# untitled.net
KiCad netlist of a schematic drawn in EAGLE
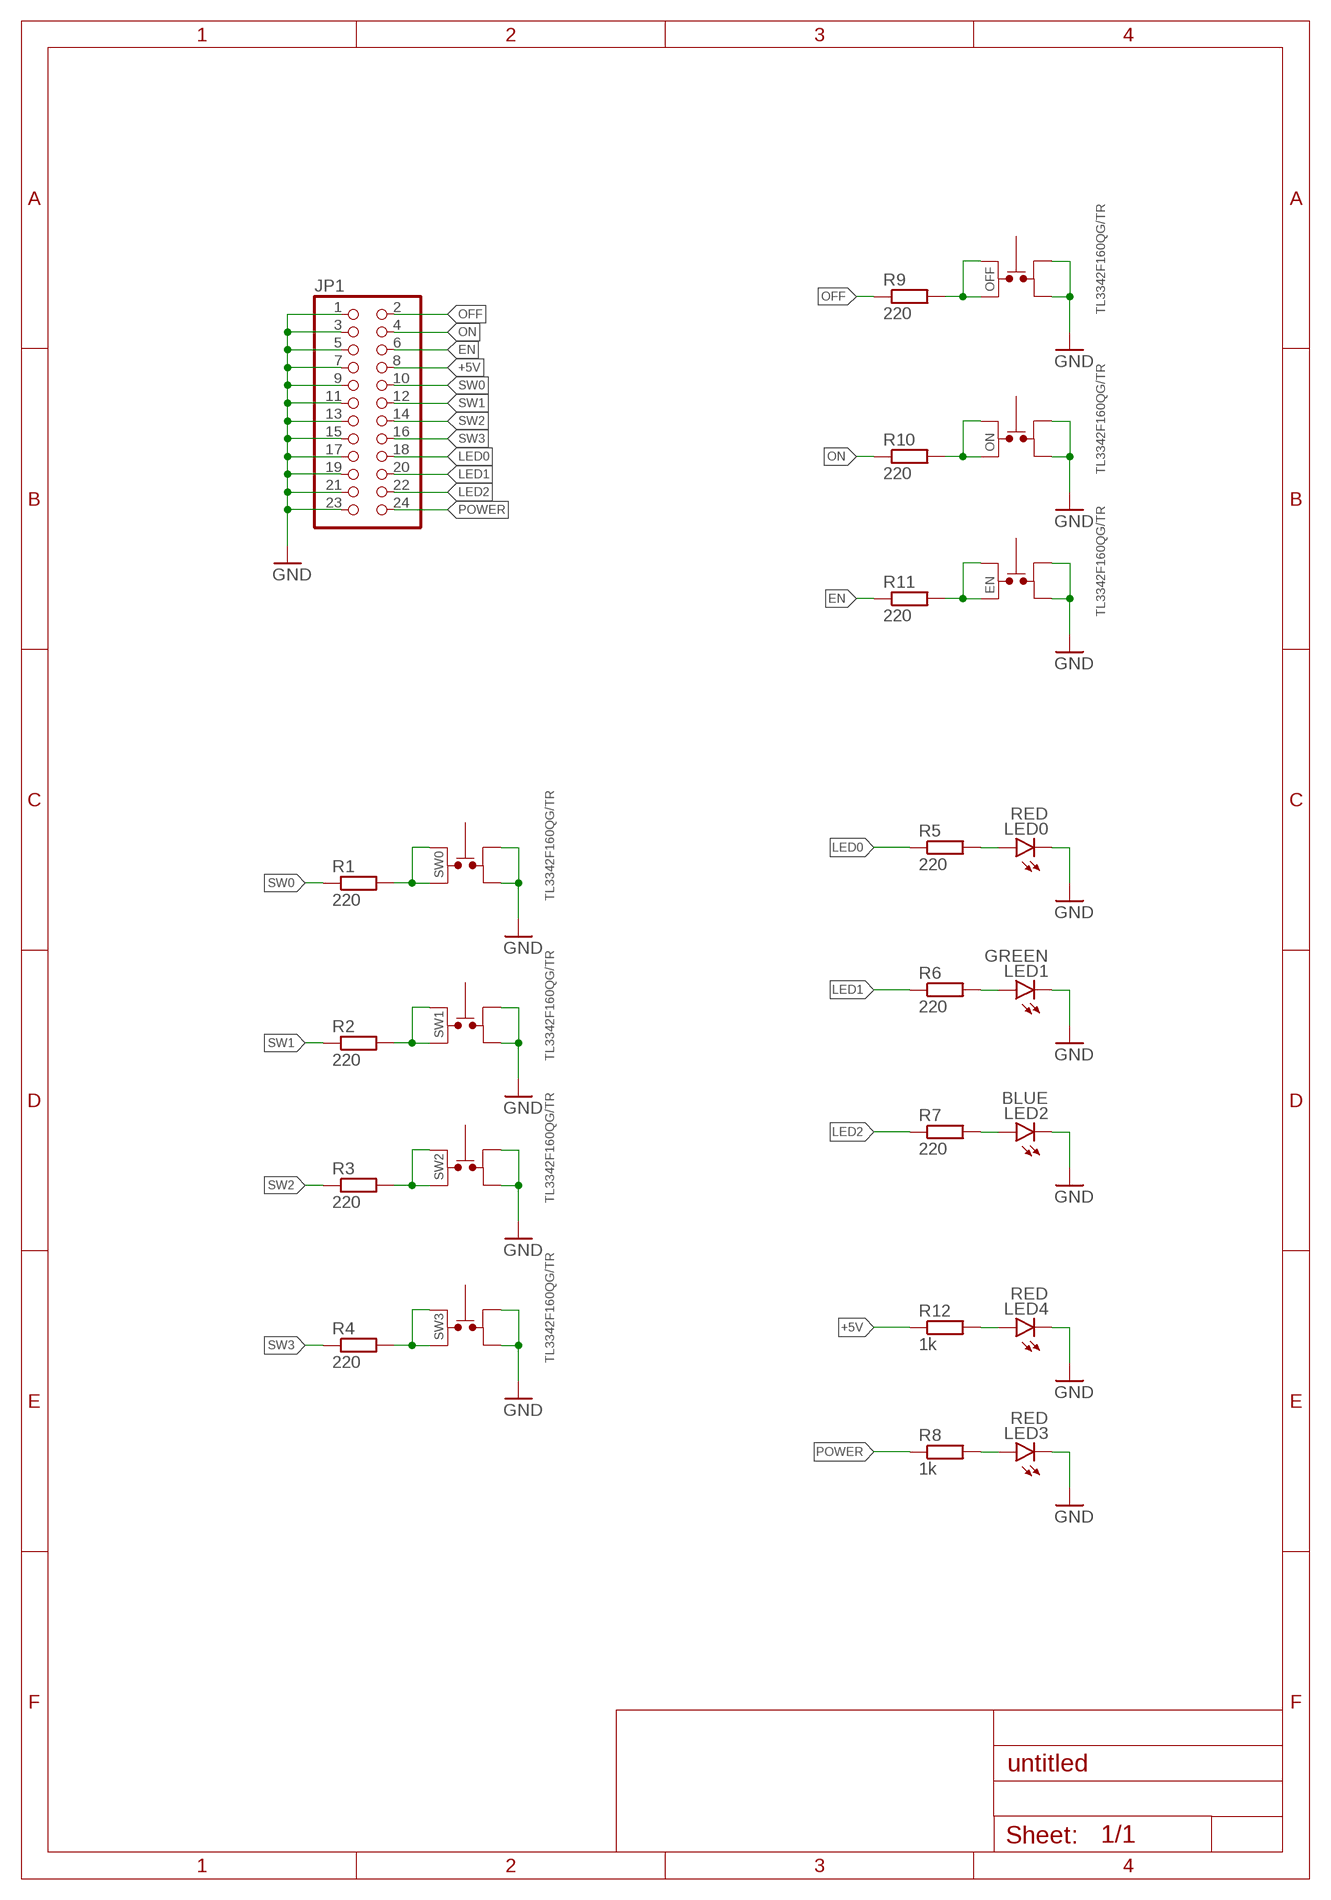
[diagram p0: schematic, sheet 1]

(export (version "E")
  (design (tool "Eeschema 10.0.6"))
  (components
    (comp (ref "EN")
      (value "TL3342F160QG/TR")
      (footprint "eagle-import:TL3342F160QG_TR")
      (fields
        (field (name "DIGI_KEY_PART_NUMBER") "EG2531CT-ND")
        (field (name "MANUFACTURER") "E-Switch")
        (field (name "CREATED_BY") "PCBLayout.com")
      )
      (libsource (lib "eagle-import") (part "TL3342F160QG/TR"))
    )
    (comp (ref "JP1")
      (value "PINHD-2X12")
      (footprint "eagle-import:2X12")
      (libsource (lib "eagle-import") (part "PINHD-2X12"))
    )
    (comp (ref "LED0")
      (value "RED")
      (footprint "eagle-import:SML0603")
      (libsource (lib "eagle-import") (part "LEDSML0603"))
    )
    (comp (ref "LED1")
      (value "GREEN")
      (footprint "eagle-import:SML0603")
      (libsource (lib "eagle-import") (part "LEDSML0603"))
    )
    (comp (ref "LED2")
      (value "BLUE")
      (footprint "eagle-import:SML0603")
      (libsource (lib "eagle-import") (part "LEDSML0603"))
    )
    (comp (ref "LED3")
      (value "RED")
      (footprint "eagle-import:SML0603")
      (libsource (lib "eagle-import") (part "LEDSML0603"))
    )
    (comp (ref "LED4")
      (value "RED")
      (footprint "eagle-import:SML0603")
      (libsource (lib "eagle-import") (part "LEDSML0603"))
    )
    (comp (ref "OFF")
      (value "TL3342F160QG/TR")
      (footprint "eagle-import:TL3342F160QG_TR")
      (fields
        (field (name "DIGI_KEY_PART_NUMBER") "EG2531CT-ND")
        (field (name "MANUFACTURER") "E-Switch")
        (field (name "CREATED_BY") "PCBLayout.com")
      )
      (libsource (lib "eagle-import") (part "TL3342F160QG/TR"))
    )
    (comp (ref "ON")
      (value "TL3342F160QG/TR")
      (footprint "eagle-import:TL3342F160QG_TR")
      (fields
        (field (name "DIGI_KEY_PART_NUMBER") "EG2531CT-ND")
        (field (name "MANUFACTURER") "E-Switch")
        (field (name "CREATED_BY") "PCBLayout.com")
      )
      (libsource (lib "eagle-import") (part "TL3342F160QG/TR"))
    )
    (comp (ref "R1")
      (value "220")
      (footprint "eagle-import:R0402")
      (libsource (lib "eagle-import") (part "R-EU_R0402"))
    )
    (comp (ref "R2")
      (value "220")
      (footprint "eagle-import:R0402")
      (libsource (lib "eagle-import") (part "R-EU_R0402"))
    )
    (comp (ref "R3")
      (value "220")
      (footprint "eagle-import:R0402")
      (libsource (lib "eagle-import") (part "R-EU_R0402"))
    )
    (comp (ref "R4")
      (value "220")
      (footprint "eagle-import:R0402")
      (libsource (lib "eagle-import") (part "R-EU_R0402"))
    )
    (comp (ref "R5")
      (value "220")
      (footprint "eagle-import:R0402")
      (libsource (lib "eagle-import") (part "R-EU_R0402"))
    )
    (comp (ref "R6")
      (value "220")
      (footprint "eagle-import:R0402")
      (libsource (lib "eagle-import") (part "R-EU_R0402"))
    )
    (comp (ref "R7")
      (value "220")
      (footprint "eagle-import:R0402")
      (libsource (lib "eagle-import") (part "R-EU_R0402"))
    )
    (comp (ref "R8")
      (value "1k")
      (footprint "eagle-import:R0402")
      (libsource (lib "eagle-import") (part "R-EU_R0402"))
    )
    (comp (ref "R9")
      (value "220")
      (footprint "eagle-import:R0402")
      (libsource (lib "eagle-import") (part "R-EU_R0402"))
    )
    (comp (ref "R10")
      (value "220")
      (footprint "eagle-import:R0402")
      (libsource (lib "eagle-import") (part "R-EU_R0402"))
    )
    (comp (ref "R11")
      (value "220")
      (footprint "eagle-import:R0402")
      (libsource (lib "eagle-import") (part "R-EU_R0402"))
    )
    (comp (ref "R12")
      (value "1k")
      (footprint "eagle-import:R0402")
      (libsource (lib "eagle-import") (part "R-EU_R0402"))
    )
    (comp (ref "SW0")
      (value "TL3342F160QG/TR")
      (footprint "eagle-import:TL3342F160QG_TR")
      (fields
        (field (name "DIGI_KEY_PART_NUMBER") "EG2531CT-ND")
        (field (name "MANUFACTURER") "E-Switch")
        (field (name "CREATED_BY") "PCBLayout.com")
      )
      (libsource (lib "eagle-import") (part "TL3342F160QG/TR"))
    )
    (comp (ref "SW1")
      (value "TL3342F160QG/TR")
      (footprint "eagle-import:TL3342F160QG_TR")
      (fields
        (field (name "DIGI_KEY_PART_NUMBER") "EG2531CT-ND")
        (field (name "MANUFACTURER") "E-Switch")
        (field (name "CREATED_BY") "PCBLayout.com")
      )
      (libsource (lib "eagle-import") (part "TL3342F160QG/TR"))
    )
    (comp (ref "SW2")
      (value "TL3342F160QG/TR")
      (footprint "eagle-import:TL3342F160QG_TR")
      (fields
        (field (name "DIGI_KEY_PART_NUMBER") "EG2531CT-ND")
        (field (name "MANUFACTURER") "E-Switch")
        (field (name "CREATED_BY") "PCBLayout.com")
      )
      (libsource (lib "eagle-import") (part "TL3342F160QG/TR"))
    )
    (comp (ref "SW3")
      (value "TL3342F160QG/TR")
      (footprint "eagle-import:TL3342F160QG_TR")
      (fields
        (field (name "DIGI_KEY_PART_NUMBER") "EG2531CT-ND")
        (field (name "MANUFACTURER") "E-Switch")
        (field (name "CREATED_BY") "PCBLayout.com")
      )
      (libsource (lib "eagle-import") (part "TL3342F160QG/TR"))
    )
  )
  (nets
    (net (code "1") (name "+5V") (class "Default")
      (node (ref "JP1") (pin "8") (pinfunction "8_8") (pintype "passive"))
      (node (ref "R12") (pin "1") (pinfunction "1_1") (pintype "passive"))
    )
    (net (code "2") (name "EN") (class "Default")
      (node (ref "JP1") (pin "6") (pinfunction "6_6") (pintype "passive"))
      (node (ref "R11") (pin "1") (pinfunction "1_1") (pintype "passive"))
    )
    (net (code "3") (name "GND") (class "Default")
      (node (ref "EN") (pin "1") (pinfunction "1_1") (pintype "passive"))
      (node (ref "EN") (pin "2") (pinfunction "2_2") (pintype "passive"))
      (node (ref "JP1") (pin "1") (pinfunction "1_1") (pintype "passive"))
      (node (ref "JP1") (pin "11") (pinfunction "11_11") (pintype "passive"))
      (node (ref "JP1") (pin "13") (pinfunction "13_13") (pintype "passive"))
      (node (ref "JP1") (pin "15") (pinfunction "15_15") (pintype "passive"))
      (node (ref "JP1") (pin "17") (pinfunction "17_17") (pintype "passive"))
      (node (ref "JP1") (pin "19") (pinfunction "19_19") (pintype "passive"))
      (node (ref "JP1") (pin "21") (pinfunction "21_21") (pintype "passive"))
      (node (ref "JP1") (pin "23") (pinfunction "23_23") (pintype "passive"))
      (node (ref "JP1") (pin "3") (pinfunction "3_3") (pintype "passive"))
      (node (ref "JP1") (pin "5") (pinfunction "5_5") (pintype "passive"))
      (node (ref "JP1") (pin "7") (pinfunction "7_7") (pintype "passive"))
      (node (ref "JP1") (pin "9") (pinfunction "9_9") (pintype "passive"))
      (node (ref "LED0") (pin "C") (pinfunction "C_C") (pintype "passive"))
      (node (ref "LED1") (pin "C") (pinfunction "C_C") (pintype "passive"))
      (node (ref "LED2") (pin "C") (pinfunction "C_C") (pintype "passive"))
      (node (ref "LED3") (pin "C") (pinfunction "C_C") (pintype "passive"))
      (node (ref "LED4") (pin "C") (pinfunction "C_C") (pintype "passive"))
      (node (ref "OFF") (pin "1") (pinfunction "1_1") (pintype "passive"))
      (node (ref "OFF") (pin "2") (pinfunction "2_2") (pintype "passive"))
      (node (ref "ON") (pin "1") (pinfunction "1_1") (pintype "passive"))
      (node (ref "ON") (pin "2") (pinfunction "2_2") (pintype "passive"))
      (node (ref "SW0") (pin "1") (pinfunction "1_1") (pintype "passive"))
      (node (ref "SW0") (pin "2") (pinfunction "2_2") (pintype "passive"))
      (node (ref "SW1") (pin "1") (pinfunction "1_1") (pintype "passive"))
      (node (ref "SW1") (pin "2") (pinfunction "2_2") (pintype "passive"))
      (node (ref "SW2") (pin "1") (pinfunction "1_1") (pintype "passive"))
      (node (ref "SW2") (pin "2") (pinfunction "2_2") (pintype "passive"))
      (node (ref "SW3") (pin "1") (pinfunction "1_1") (pintype "passive"))
      (node (ref "SW3") (pin "2") (pinfunction "2_2") (pintype "passive"))
    )
    (net (code "4") (name "LED0") (class "Default")
      (node (ref "JP1") (pin "18") (pinfunction "18_18") (pintype "passive"))
      (node (ref "R5") (pin "1") (pinfunction "1_1") (pintype "passive"))
    )
    (net (code "5") (name "LED1") (class "Default")
      (node (ref "JP1") (pin "20") (pinfunction "20_20") (pintype "passive"))
      (node (ref "R6") (pin "1") (pinfunction "1_1") (pintype "passive"))
    )
    (net (code "6") (name "LED2") (class "Default")
      (node (ref "JP1") (pin "22") (pinfunction "22_22") (pintype "passive"))
      (node (ref "R7") (pin "1") (pinfunction "1_1") (pintype "passive"))
    )
    (net (code "7") (name "Net-(EN-Pad3)") (class "Default")
      (node (ref "EN") (pin "3") (pinfunction "3_3") (pintype "passive"))
      (node (ref "EN") (pin "4") (pinfunction "4_4") (pintype "passive"))
      (node (ref "R11") (pin "2") (pinfunction "2_2") (pintype "passive"))
    )
    (net (code "8") (name "Net-(LED0-PadA)") (class "Default")
      (node (ref "LED0") (pin "A") (pinfunction "A_A") (pintype "passive"))
      (node (ref "R5") (pin "2") (pinfunction "2_2") (pintype "passive"))
    )
    (net (code "9") (name "Net-(LED1-PadA)") (class "Default")
      (node (ref "LED1") (pin "A") (pinfunction "A_A") (pintype "passive"))
      (node (ref "R6") (pin "2") (pinfunction "2_2") (pintype "passive"))
    )
    (net (code "10") (name "Net-(LED2-PadA)") (class "Default")
      (node (ref "LED2") (pin "A") (pinfunction "A_A") (pintype "passive"))
      (node (ref "R7") (pin "2") (pinfunction "2_2") (pintype "passive"))
    )
    (net (code "11") (name "Net-(LED3-PadA)") (class "Default")
      (node (ref "LED3") (pin "A") (pinfunction "A_A") (pintype "passive"))
      (node (ref "R8") (pin "2") (pinfunction "2_2") (pintype "passive"))
    )
    (net (code "12") (name "Net-(LED4-PadA)") (class "Default")
      (node (ref "LED4") (pin "A") (pinfunction "A_A") (pintype "passive"))
      (node (ref "R12") (pin "2") (pinfunction "2_2") (pintype "passive"))
    )
    (net (code "13") (name "Net-(OFF-Pad3)") (class "Default")
      (node (ref "OFF") (pin "3") (pinfunction "3_3") (pintype "passive"))
      (node (ref "OFF") (pin "4") (pinfunction "4_4") (pintype "passive"))
      (node (ref "R9") (pin "2") (pinfunction "2_2") (pintype "passive"))
    )
    (net (code "14") (name "Net-(ON-Pad3)") (class "Default")
      (node (ref "ON") (pin "3") (pinfunction "3_3") (pintype "passive"))
      (node (ref "ON") (pin "4") (pinfunction "4_4") (pintype "passive"))
      (node (ref "R10") (pin "2") (pinfunction "2_2") (pintype "passive"))
    )
    (net (code "15") (name "Net-(R1-Pad2)") (class "Default")
      (node (ref "R1") (pin "2") (pinfunction "2_2") (pintype "passive"))
      (node (ref "SW0") (pin "3") (pinfunction "3_3") (pintype "passive"))
      (node (ref "SW0") (pin "4") (pinfunction "4_4") (pintype "passive"))
    )
    (net (code "16") (name "Net-(R2-Pad2)") (class "Default")
      (node (ref "R2") (pin "2") (pinfunction "2_2") (pintype "passive"))
      (node (ref "SW1") (pin "3") (pinfunction "3_3") (pintype "passive"))
      (node (ref "SW1") (pin "4") (pinfunction "4_4") (pintype "passive"))
    )
    (net (code "17") (name "Net-(R3-Pad2)") (class "Default")
      (node (ref "R3") (pin "2") (pinfunction "2_2") (pintype "passive"))
      (node (ref "SW2") (pin "3") (pinfunction "3_3") (pintype "passive"))
      (node (ref "SW2") (pin "4") (pinfunction "4_4") (pintype "passive"))
    )
    (net (code "18") (name "Net-(R4-Pad2)") (class "Default")
      (node (ref "R4") (pin "2") (pinfunction "2_2") (pintype "passive"))
      (node (ref "SW3") (pin "3") (pinfunction "3_3") (pintype "passive"))
      (node (ref "SW3") (pin "4") (pinfunction "4_4") (pintype "passive"))
    )
    (net (code "19") (name "OFF") (class "Default")
      (node (ref "JP1") (pin "2") (pinfunction "2_2") (pintype "passive"))
      (node (ref "R9") (pin "1") (pinfunction "1_1") (pintype "passive"))
    )
    (net (code "20") (name "ON") (class "Default")
      (node (ref "JP1") (pin "4") (pinfunction "4_4") (pintype "passive"))
      (node (ref "R10") (pin "1") (pinfunction "1_1") (pintype "passive"))
    )
    (net (code "21") (name "POWER") (class "Default")
      (node (ref "JP1") (pin "24") (pinfunction "24_24") (pintype "passive"))
      (node (ref "R8") (pin "1") (pinfunction "1_1") (pintype "passive"))
    )
    (net (code "22") (name "SW0") (class "Default")
      (node (ref "JP1") (pin "10") (pinfunction "10_10") (pintype "passive"))
      (node (ref "R1") (pin "1") (pinfunction "1_1") (pintype "passive"))
    )
    (net (code "23") (name "SW1") (class "Default")
      (node (ref "JP1") (pin "12") (pinfunction "12_12") (pintype "passive"))
      (node (ref "R2") (pin "1") (pinfunction "1_1") (pintype "passive"))
    )
    (net (code "24") (name "SW2") (class "Default")
      (node (ref "JP1") (pin "14") (pinfunction "14_14") (pintype "passive"))
      (node (ref "R3") (pin "1") (pinfunction "1_1") (pintype "passive"))
    )
    (net (code "25") (name "SW3") (class "Default")
      (node (ref "JP1") (pin "16") (pinfunction "16_16") (pintype "passive"))
      (node (ref "R4") (pin "1") (pinfunction "1_1") (pintype "passive"))
    )
  )
)
